# rev_A.net
KiCad netlist of a schematic drawn in EAGLE
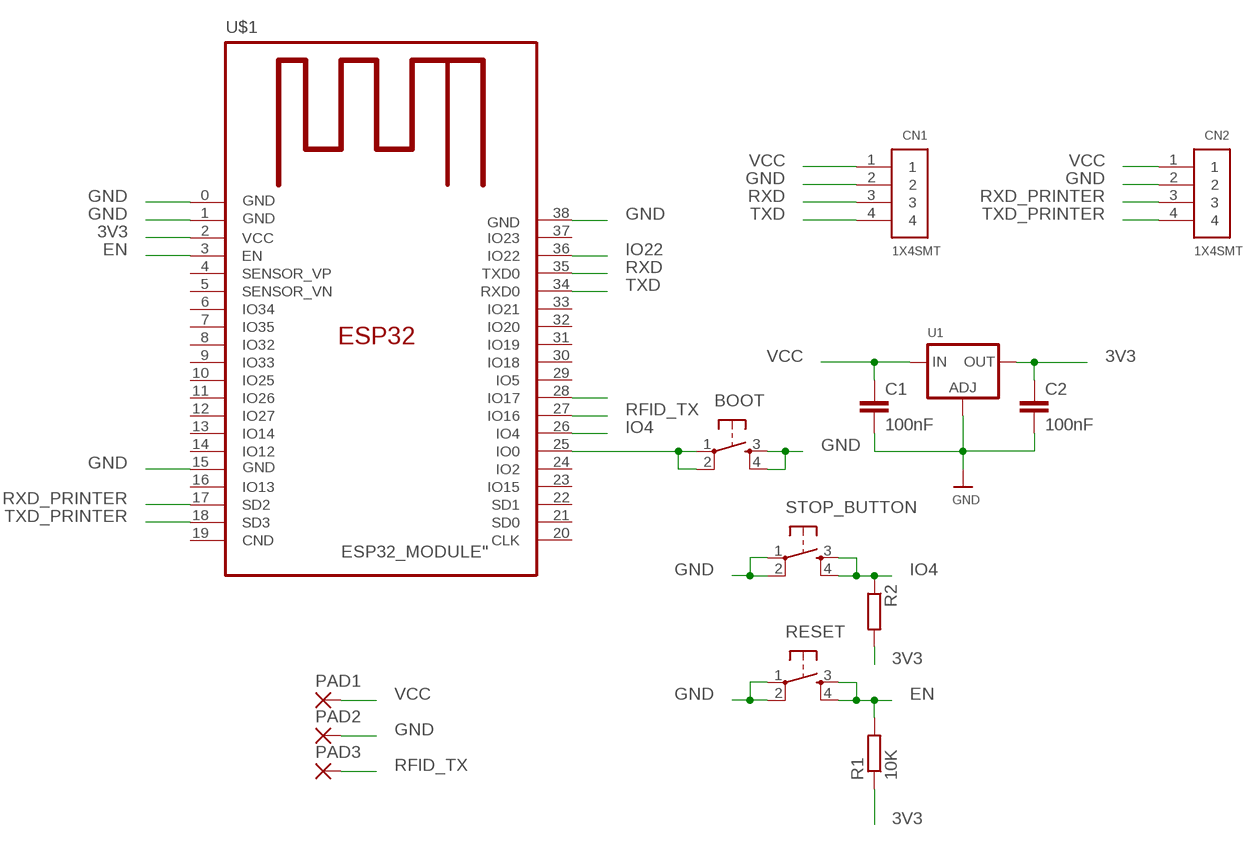
[diagram p0: schematic, sheet 1]

(export (version "E")
  (design (tool "Eeschema 10.0.6"))
  (components
    (comp (ref "BOOT")
      (value "TACTILE_SWITCHE_5X5_MICRO\"")
      (footprint "eagle-import:TACTILE_SWITCH_5X5_MICRO")
      (libsource (lib "eagle-import") (part "TACTILE_SWITCHE_5X5_MICRO{dblquote}"))
    )
    (comp (ref "C1")
      (value "100nF")
      (footprint "eagle-import:C0805")
      (libsource (lib "eagle-import") (part "C-EUC0805"))
    )
    (comp (ref "C2")
      (value "100nF")
      (footprint "eagle-import:C0805")
      (libsource (lib "eagle-import") (part "C-EUC0805"))
    )
    (comp (ref "CN1")
      (value "1X4SMT")
      (footprint "eagle-import:1X4-SMT")
      (libsource (lib "eagle-import") (part "1X4SMT"))
    )
    (comp (ref "CN2")
      (value "1X4SMT")
      (footprint "eagle-import:1X4-SMT")
      (libsource (lib "eagle-import") (part "1X4SMT"))
    )
    (comp (ref "PAD1")
      (value "SMD2")
      (footprint "eagle-import:SMD1,27-2,54")
      (libsource (lib "eagle-import") (part "SMD2"))
    )
    (comp (ref "PAD2")
      (value "SMD2")
      (footprint "eagle-import:SMD1,27-2,54")
      (libsource (lib "eagle-import") (part "SMD2"))
    )
    (comp (ref "PAD3")
      (value "SMD2")
      (footprint "eagle-import:SMD1,27-2,54")
      (libsource (lib "eagle-import") (part "SMD2"))
    )
    (comp (ref "R1")
      (value "10K")
      (footprint "eagle-import:R0805")
      (libsource (lib "eagle-import") (part "R-EU_R0805"))
    )
    (comp (ref "R2")
      (value "10K")
      (footprint "eagle-import:R0805")
      (libsource (lib "eagle-import") (part "R-EU_R0805"))
    )
    (comp (ref "RESET")
      (value "TACTILE_SWITCHE_5X5_MICRO\"")
      (footprint "eagle-import:TACTILE_SWITCH_5X5_MICRO")
      (libsource (lib "eagle-import") (part "TACTILE_SWITCHE_5X5_MICRO{dblquote}"))
    )
    (comp (ref "STOP_BUTTON")
      (value "TACTILE_SWITCH_THT_")
      (footprint "eagle-import:TACTILE_SWICTH_THT")
      (libsource (lib "eagle-import") (part "TACTILE_SWITCH_THT_"))
    )
    (comp (ref "U$1")
      (value "ESP32_MODULE\"")
      (footprint "eagle-import:ESP32_MODULE")
      (libsource (lib "eagle-import") (part "ESP32_MODULE{dblquote}"))
    )
    (comp (ref "U1")
      (value "LM1117SOT223-REFLOW")
      (footprint "eagle-import:SOT223-R")
      (libsource (lib "eagle-import") (part "LM1117SOT223-REFLOW"))
    )
  )
  (nets
    (net (code "1") (name "/3V3") (class "Default")
      (node (ref "C2") (pin "1") (pinfunction "1_1") (pintype "passive"))
      (node (ref "R1") (pin "1") (pinfunction "1_1") (pintype "passive"))
      (node (ref "R2") (pin "2") (pinfunction "2_2") (pintype "passive"))
      (node (ref "U$1") (pin "2") (pinfunction "VCC_2") (pintype "power_in"))
      (node (ref "U1") (pin "2") (pinfunction "OUT_2") (pintype "passive"))
    )
    (net (code "2") (name "/EN") (class "Default")
      (node (ref "R1") (pin "2") (pinfunction "2_2") (pintype "passive"))
      (node (ref "RESET") (pin "3") (pinfunction "3_3") (pintype "passive"))
      (node (ref "RESET") (pin "4") (pinfunction "4_4") (pintype "passive"))
      (node (ref "U$1") (pin "3") (pinfunction "EN_3") (pintype "bidirectional"))
    )
    (net (code "3") (name "/IO4") (class "Default")
      (node (ref "R2") (pin "1") (pinfunction "1_1") (pintype "passive"))
      (node (ref "STOP_BUTTON") (pin "3") (pinfunction "3_3") (pintype "passive"))
      (node (ref "STOP_BUTTON") (pin "4") (pinfunction "4_4") (pintype "passive"))
      (node (ref "U$1") (pin "26") (pinfunction "IO4_26") (pintype "bidirectional"))
    )
    (net (code "4") (name "/IO22") (class "Default")
      (node (ref "U$1") (pin "36") (pinfunction "IO22_36") (pintype "bidirectional"))
    )
    (net (code "5") (name "/RFID_TX") (class "Default")
      (node (ref "PAD3") (pin "1") (pinfunction "P_1") (pintype "passive"))
      (node (ref "U$1") (pin "27") (pinfunction "IO16_27") (pintype "bidirectional"))
    )
    (net (code "6") (name "/RXD") (class "Default")
      (node (ref "CN1") (pin "3") (pinfunction "3_3") (pintype "bidirectional"))
      (node (ref "U$1") (pin "35") (pinfunction "TXD0_35") (pintype "bidirectional"))
    )
    (net (code "7") (name "/RXD_PRINTER") (class "Default")
      (node (ref "CN2") (pin "3") (pinfunction "3_3") (pintype "bidirectional"))
      (node (ref "U$1") (pin "17") (pinfunction "SD2_17") (pintype "bidirectional"))
    )
    (net (code "8") (name "/TXD") (class "Default")
      (node (ref "CN1") (pin "4") (pinfunction "4_4") (pintype "bidirectional"))
      (node (ref "U$1") (pin "34") (pinfunction "RXD0_34") (pintype "bidirectional"))
    )
    (net (code "9") (name "/TXD_PRINTER") (class "Default")
      (node (ref "CN2") (pin "4") (pinfunction "4_4") (pintype "bidirectional"))
      (node (ref "U$1") (pin "18") (pinfunction "SD3_18") (pintype "bidirectional"))
    )
    (net (code "10") (name "/VCC") (class "Default")
      (node (ref "C1") (pin "1") (pinfunction "1_1") (pintype "passive"))
      (node (ref "CN1") (pin "1") (pinfunction "1_1") (pintype "bidirectional"))
      (node (ref "CN2") (pin "1") (pinfunction "1_1") (pintype "bidirectional"))
      (node (ref "PAD1") (pin "1") (pinfunction "P_1") (pintype "passive"))
      (node (ref "U1") (pin "3") (pinfunction "IN_3") (pintype "input"))
    )
    (net (code "11") (name "GND") (class "Default")
      (node (ref "BOOT") (pin "3") (pinfunction "3_3") (pintype "passive"))
      (node (ref "BOOT") (pin "4") (pinfunction "4_4") (pintype "passive"))
      (node (ref "C1") (pin "2") (pinfunction "2_2") (pintype "passive"))
      (node (ref "C2") (pin "2") (pinfunction "2_2") (pintype "passive"))
      (node (ref "CN1") (pin "2") (pinfunction "2_2") (pintype "bidirectional"))
      (node (ref "CN2") (pin "2") (pinfunction "2_2") (pintype "bidirectional"))
      (node (ref "PAD2") (pin "1") (pinfunction "P_1") (pintype "passive"))
      (node (ref "RESET") (pin "1") (pinfunction "1_1") (pintype "passive"))
      (node (ref "RESET") (pin "2") (pinfunction "2_2") (pintype "passive"))
      (node (ref "STOP_BUTTON") (pin "1") (pinfunction "1_1") (pintype "passive"))
      (node (ref "STOP_BUTTON") (pin "2") (pinfunction "2_2") (pintype "passive"))
      (node (ref "U$1") (pin "0") (pinfunction "GND_0") (pintype "power_in"))
      (node (ref "U$1") (pin "1") (pinfunction "GND_1") (pintype "power_in"))
      (node (ref "U$1") (pin "15") (pinfunction "GND_15") (pintype "power_in"))
      (node (ref "U$1") (pin "38") (pinfunction "GND_38") (pintype "power_in"))
      (node (ref "U1") (pin "1") (pinfunction "ADJ_1") (pintype "input"))
    )
    (net (code "12") (name "Net-(U$1-IO0)") (class "Default")
      (node (ref "BOOT") (pin "1") (pinfunction "1_1") (pintype "passive"))
      (node (ref "BOOT") (pin "2") (pinfunction "2_2") (pintype "passive"))
      (node (ref "U$1") (pin "25") (pinfunction "IO0_25") (pintype "bidirectional"))
    )
    (net (code "13") (name "unconnected-(U$1-CLK-Pad20)") (class "Default")
      (node (ref "U$1") (pin "20") (pinfunction "CLK_20") (pintype "bidirectional"))
    )
    (net (code "14") (name "unconnected-(U$1-CND-Pad19)") (class "Default")
      (node (ref "U$1") (pin "19") (pinfunction "CND_19") (pintype "bidirectional"))
    )
    (net (code "15") (name "unconnected-(U$1-IO2-Pad24)") (class "Default")
      (node (ref "U$1") (pin "24") (pinfunction "IO2_24") (pintype "bidirectional"))
    )
    (net (code "16") (name "unconnected-(U$1-IO5-Pad29)") (class "Default")
      (node (ref "U$1") (pin "29") (pinfunction "IO5_29") (pintype "bidirectional"))
    )
    (net (code "17") (name "unconnected-(U$1-IO12-Pad14)") (class "Default")
      (node (ref "U$1") (pin "14") (pinfunction "IO12_14") (pintype "bidirectional"))
    )
    (net (code "18") (name "unconnected-(U$1-IO13-Pad16)") (class "Default")
      (node (ref "U$1") (pin "16") (pinfunction "IO13_16") (pintype "bidirectional"))
    )
    (net (code "19") (name "unconnected-(U$1-IO14-Pad13)") (class "Default")
      (node (ref "U$1") (pin "13") (pinfunction "IO14_13") (pintype "bidirectional"))
    )
    (net (code "20") (name "unconnected-(U$1-IO15-Pad23)") (class "Default")
      (node (ref "U$1") (pin "23") (pinfunction "IO15_23") (pintype "bidirectional"))
    )
    (net (code "21") (name "unconnected-(U$1-IO17-Pad28)") (class "Default")
      (node (ref "U$1") (pin "28") (pinfunction "IO17_28") (pintype "bidirectional"))
    )
    (net (code "22") (name "unconnected-(U$1-IO18-Pad30)") (class "Default")
      (node (ref "U$1") (pin "30") (pinfunction "IO18_30") (pintype "bidirectional"))
    )
    (net (code "23") (name "unconnected-(U$1-IO19-Pad31)") (class "Default")
      (node (ref "U$1") (pin "31") (pinfunction "IO19_31") (pintype "bidirectional"))
    )
    (net (code "24") (name "unconnected-(U$1-IO20-Pad32)") (class "Default")
      (node (ref "U$1") (pin "32") (pinfunction "IO20_32") (pintype "bidirectional"))
    )
    (net (code "25") (name "unconnected-(U$1-IO21-Pad33)") (class "Default")
      (node (ref "U$1") (pin "33") (pinfunction "IO21_33") (pintype "bidirectional"))
    )
    (net (code "26") (name "unconnected-(U$1-IO23-Pad37)") (class "Default")
      (node (ref "U$1") (pin "37") (pinfunction "IO23_37") (pintype "bidirectional"))
    )
    (net (code "27") (name "unconnected-(U$1-IO25-Pad10)") (class "Default")
      (node (ref "U$1") (pin "10") (pinfunction "IO25_10") (pintype "bidirectional"))
    )
    (net (code "28") (name "unconnected-(U$1-IO26-Pad11)") (class "Default")
      (node (ref "U$1") (pin "11") (pinfunction "IO26_11") (pintype "bidirectional"))
    )
    (net (code "29") (name "unconnected-(U$1-IO27-Pad12)") (class "Default")
      (node (ref "U$1") (pin "12") (pinfunction "IO27_12") (pintype "bidirectional"))
    )
    (net (code "30") (name "unconnected-(U$1-IO32-Pad8)") (class "Default")
      (node (ref "U$1") (pin "8") (pinfunction "IO32_8") (pintype "bidirectional"))
    )
    (net (code "31") (name "unconnected-(U$1-IO33-Pad9)") (class "Default")
      (node (ref "U$1") (pin "9") (pinfunction "IO33_9") (pintype "bidirectional"))
    )
    (net (code "32") (name "unconnected-(U$1-IO34-Pad6)") (class "Default")
      (node (ref "U$1") (pin "6") (pinfunction "IO34_6") (pintype "bidirectional"))
    )
    (net (code "33") (name "unconnected-(U$1-IO35-Pad7)") (class "Default")
      (node (ref "U$1") (pin "7") (pinfunction "IO35_7") (pintype "bidirectional"))
    )
    (net (code "34") (name "unconnected-(U$1-SD0-Pad21)") (class "Default")
      (node (ref "U$1") (pin "21") (pinfunction "SD0_21") (pintype "bidirectional"))
    )
    (net (code "35") (name "unconnected-(U$1-SD1-Pad22)") (class "Default")
      (node (ref "U$1") (pin "22") (pinfunction "SD1_22") (pintype "bidirectional"))
    )
    (net (code "36") (name "unconnected-(U$1-SENSOR_VN-Pad5)") (class "Default")
      (node (ref "U$1") (pin "5") (pinfunction "SENSOR_VN_5") (pintype "bidirectional"))
    )
    (net (code "37") (name "unconnected-(U$1-SENSOR_VP-Pad4)") (class "Default")
      (node (ref "U$1") (pin "4") (pinfunction "SENSOR_VP_4") (pintype "bidirectional"))
    )
  )
)
